# Power_Supply.net
KiCad netlist of a schematic drawn in Altium Designer
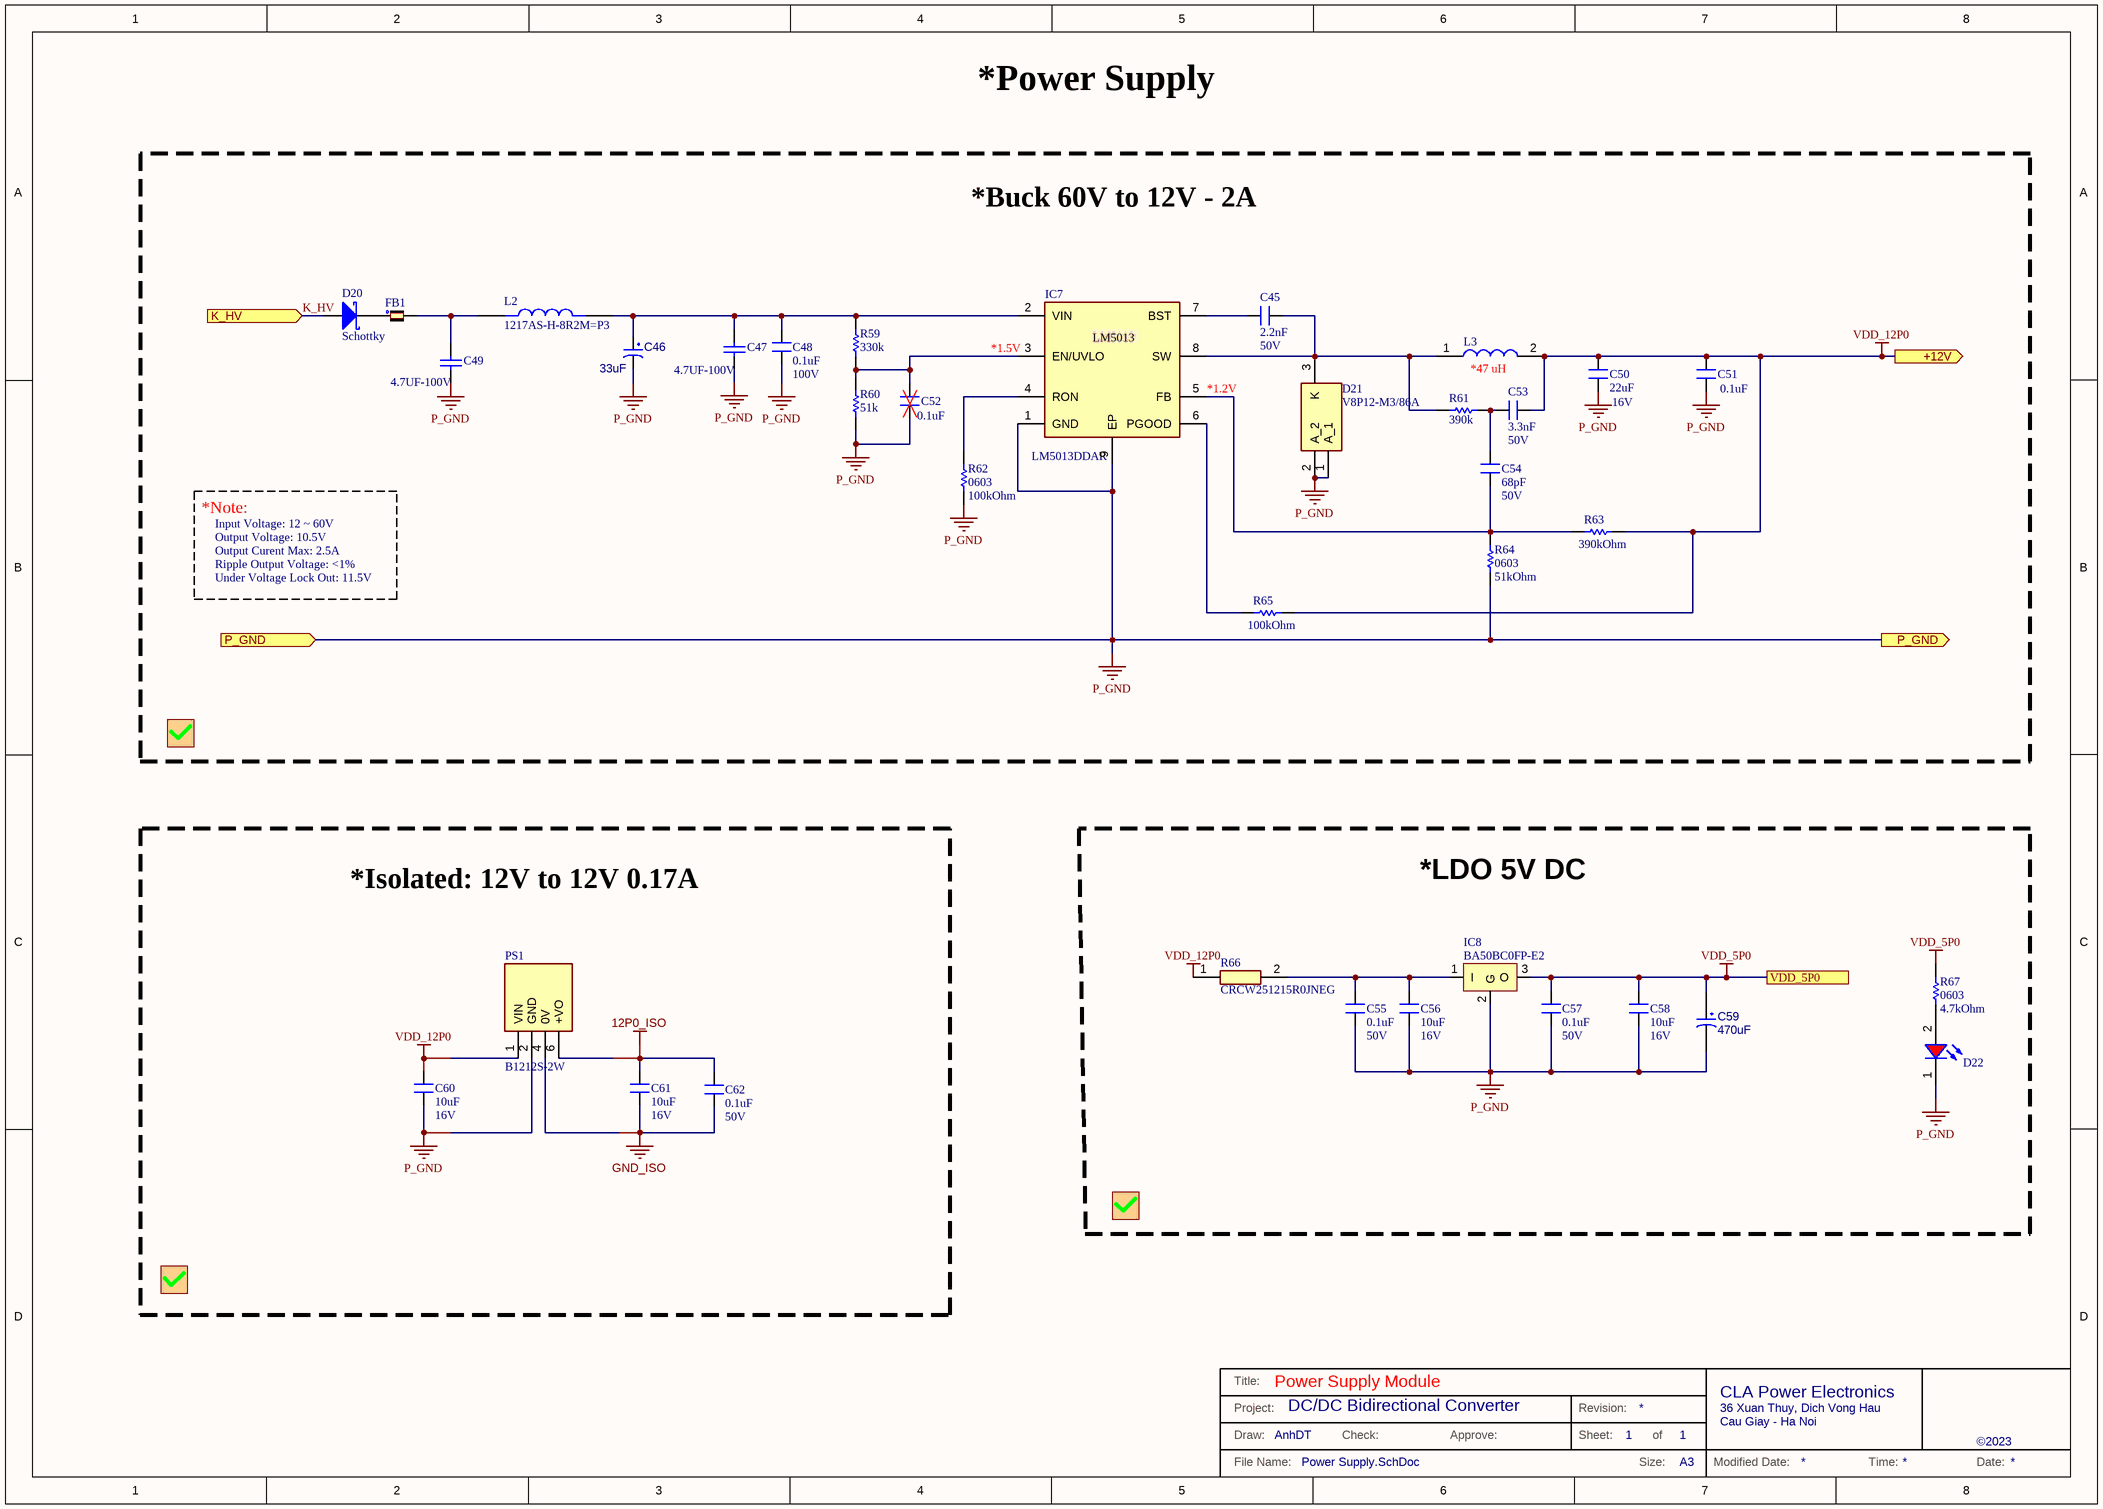
[diagram p0: Power Supply.SchDoc]

(export (version "E")
  (design (tool "Eeschema 10.0.6"))
  (components
    (comp (ref "C45")
      (value "2.2nF")
      (footprint "C_0603")
      (description "CAP CER 2.2nF 50V X7R 0805")
      (fields
        (field (name "MANUFACTURER") "Samsung Electro-Mechanics")
        (field (name "PART NUMBER") "C0805C222J5GEC7800")
        (field (name "ALTIUM_VALUE") "50V")
      )
      (libsource (lib "S1200_Capacitor") (part "Cap_Cer_0805_10pF"))
    )
    (comp (ref "C46")
      (value "33uF")
      (footprint "C_ALU_TH_8p0D11p5")
      (description "CAP ALUM 33UF 20% 80V RADIAL")
      (fields (field (name "MANUFACTURER") "PANASONIC") (field (name "PART NUMBER") "80ZLH33MEFC6.3X11"))
      (libsource (lib "Selex_Component_Lib") (part "Cap_Alu_TH_8P0D3P5_22uF"))
    )
    (comp (ref "C47")
      (value "4.7UF-100V")
      (footprint "C_1210")
      (description "CAP CER 4.7uF 80V X7R 1210")
      (fields
        (field (name "PART NUMBER") "GRM32ER71K475KE14L")
        (field (name "MANUFACTURER") "TDK Corporation")
      )
      (libsource (lib "DC_DC_Power_V3.0") (part "Cap 1210"))
    )
    (comp (ref "C48")
      (value "0.1uF")
      (footprint "C_0805")
      (description "CAP CER 0.1uF 100V X7R 0805")
      (fields (field (name "MANUFACTURER") "Samsung Electro-Mechanics") (field (name "ALTIUM_VALUE") "100V"))
      (libsource (lib "S1200_Capacitor") (part "Cap_Cer_0805_10pF"))
    )
    (comp (ref "C49")
      (value "4.7UF-100V")
      (footprint "C_1210")
      (description "CAP CER 4.7uF 80V X7R 1210")
      (fields
        (field (name "PART NUMBER") "GRM32ER71K475KE14L")
        (field (name "MANUFACTURER") "TDK Corporation")
      )
      (libsource (lib "DC_DC_Power_V3.0") (part "Cap 1210"))
    )
    (comp (ref "C50")
      (value "22uF")
      (footprint "C_1210")
      (description "CAP CER 22uF 16V X7R 1210")
      (fields
        (field (name "MANUFACTURER") "Samsung Electro-Mechanics")
        (field (name "PART NUMBER") "CL32A226KOJNNNE")
        (field (name "ALTIUM_VALUE") "16V")
      )
      (libsource (lib "S1200_Capacitor") (part "Cap_Cer_0805_10pF"))
    )
    (comp (ref "C51")
      (value "0.1uF")
      (footprint "C_0603")
      (description "CAP CER 0.1UF 25V X8R 0603")
      (fields
        (field (name "MANUFACTURER") "Murata Electronics")
        (field (name "PART NUMBER") "GCM188R91E104KA37J")
      )
      (libsource (lib "S1200_Capacitor") (part "Cap_Cer_0603_0.1uF_25V"))
    )
    (comp (ref "C52")
      (value "0.1uF")
      (footprint "C_0603")
      (description "CAP CER 0.1UF 100V X7R 0603")
      (fields
        (field (name "MANUFACTURER") "Murata Electronics")
        (field (name "PART NUMBER") "GRM188R72A104KA35D")
      )
      (libsource (lib "S1200_Capacitor") (part "Cap_Cer_0603_0.1uF_100V"))
    )
    (comp (ref "C53")
      (value "3.3nF")
      (footprint "C_0603")
      (description "CAP CER 0805 3.3NF 50V C0G 1%")
      (fields
        (field (name "MANUFACTURER") "Kemet")
        (field (name "PART NUMBER") "C0805C332F5GECAUTO")
        (field (name "ALTIUM_VALUE") "50V")
      )
      (libsource (lib "S1200_Capacitor") (part "Cap_Cer_0805_10pF"))
    )
    (comp (ref "C54")
      (value "68pF")
      (footprint "C_0603")
      (description "CAP CER 68pF 50V C0G 0603")
      (fields
        (field (name "MANUFACTURER") "Kemet")
        (field (name "PART NUMBER") "CL10C680JB81PNC")
        (field (name "ALTIUM_VALUE") "50V")
      )
      (libsource (lib "S1200_Capacitor") (part "Cap_Cer_0805_10pF"))
    )
    (comp (ref "C55")
      (value "0.1uF")
      (footprint "C_0603")
      (description "CAP CER 0.1uF 50V X7R 0603")
      (fields
        (field (name "MANUFACTURER") "Kemet")
        (field (name "PART NUMBER") "CL10C680JB81PNC")
        (field (name "ALTIUM_VALUE") "50V")
      )
      (libsource (lib "S1200_Capacitor") (part "Cap_Cer_0805_10pF"))
    )
    (comp (ref "C56")
      (value "10uF")
      (footprint "C_0805")
      (description "CAP CER 10uF 16V X7R 0805")
      (fields
        (field (name "MANUFACTURER") "Kemet")
        (field (name "PART NUMBER") "CL21A106KOCLRNC")
        (field (name "ALTIUM_VALUE") "16V")
      )
      (libsource (lib "S1200_Capacitor") (part "Cap_Cer_0805_10pF"))
    )
    (comp (ref "C57")
      (value "0.1uF")
      (footprint "C_0603")
      (description "CAP CER 0.1uF 50V X7R 0603")
      (fields
        (field (name "MANUFACTURER") "Kemet")
        (field (name "PART NUMBER") "CL10C680JB81PNC")
        (field (name "ALTIUM_VALUE") "50V")
      )
      (libsource (lib "S1200_Capacitor") (part "Cap_Cer_0805_10pF"))
    )
    (comp (ref "C58")
      (value "10uF")
      (footprint "C_0805")
      (description "CAP CER 10uF 16V X7R 0805")
      (fields
        (field (name "MANUFACTURER") "Kemet")
        (field (name "PART NUMBER") "CL21A106KOCLRNC")
        (field (name "ALTIUM_VALUE") "16V")
      )
      (libsource (lib "S1200_Capacitor") (part "Cap_Cer_0805_10pF"))
    )
    (comp (ref "C59")
      (value "470uF")
      (footprint "C_ALU_TH_8p0D11p5")
      (description "CAP ALUM 470UF 20% 25V RADIAL")
      (fields (field (name "MANUFACTURER") "Rubycon") (field (name "PART NUMBER") "16YXJ220MT16.3X11"))
      (libsource (lib "Selex_Component_Lib") (part "Cap_Alu_TH_8P0D3P5"))
    )
    (comp (ref "C60")
      (value "10uF")
      (footprint "C_0805")
      (description "CAP CER 2.2uF 50V X7R 0805")
      (fields
        (field (name "MANUFACTURER") "Samsung Electro-Mechanics")
        (field (name "PART NUMBER") "CL31B225KBHNNNE")
        (field (name "ALTIUM_VALUE") "16V")
      )
      (libsource (lib "S1200_Capacitor") (part "Cap_Cer_0805_10pF"))
    )
    (comp (ref "C61")
      (value "10uF")
      (footprint "C_0805")
      (description "CAP CER 4.7uF 50V X7R 0805")
      (fields
        (field (name "MANUFACTURER") "Samsung Electro-Mechanics")
        (field (name "PART NUMBER") "CL31B225KBHNNNE")
        (field (name "ALTIUM_VALUE") "16V")
      )
      (libsource (lib "S1200_Capacitor") (part "Cap_Cer_0805_10pF"))
    )
    (comp (ref "C62")
      (value "0.1uF")
      (footprint "C_0603")
      (description "CAP CER 0.1uF 50V X7R 0603")
      (fields
        (field (name "MANUFACTURER") "Kemet")
        (field (name "PART NUMBER") "CL10C680JB81PNC")
        (field (name "ALTIUM_VALUE") "50V")
      )
      (libsource (lib "S1200_Capacitor") (part "Cap_Cer_0805_10pF"))
    )
    (comp (ref "D20")
      (value "Schottky")
      (footprint "DIODE_Schottky_DO214")
      (description "DIODE SCHOTTKY 100V 3A SMA")
      (fields (field (name "MANUFACTURER") "SMC Diode Solutions") (field (name "PART NUMBER") "SS310"))
      (libsource (lib "S1500_Diode") (part "SS34"))
    )
    (comp (ref "D21")
      (value "V8P12-M3/86A")
      (footprint "V8P12M386A")
      (description "DIODE SCHOTTKY 120V 8A TO277A")
      (fields (field (name "MOUSER PART NUMBER") "78-V8P12-M3/86A"))
      (libsource (lib "*") (part "V8P12-M3_86A"))
    )
    (comp (ref "D22")
      (value "LED-SMD")
      (footprint "SM-LED-0805-Red")
      (description "LED RED DIFFUSED 0805 SMD")
      (fields
        (field (name "MANUFACTURER") "OSRAM Opto Semiconductors Inc.")
        (field (name "PART NUMBER") "LS R976-NR-1")
      )
      (libsource (lib "Sync_Buck") (part "LED-SMD"))
    )
    (comp (ref "FB1")
      (value "FerriteBead_1206_270Ohm")
      (footprint "FERRITEBEAD_1206")
      (description "FERRITE BEAD 270 OHM 1206 1LN")
      (fields
        (field (name "MANUFACTURER") "Murata Electronics")
        (field (name "PART NUMBER") "BLM31KN271SH1L")
      )
      (libsource (lib "S1100_Resistor_FerriteBead") (part "FerriteBead_1206_270Ohm"))
    )
    (comp (ref "IC7")
      (value "LM5013DDAR")
      (footprint "SOIC127P600X170-9N")
      (description "IC REG BUCK ADJ 3.5A 8SO PWR")
      (libsource (lib "Tienanh") (part "LM5012DDAR"))
    )
    (comp (ref "IC8")
      (value "BA50BC0FP-E2")
      (footprint "TO252-123")
      (description "IC REG LINEAR 5V 1A TO252-2")
      (libsource (lib "Motor Control SELEX MOTORS JSC") (part "BA50BC0FP-E2"))
    )
    (comp (ref "L2")
      (value "1217AS-H-8R2M=P3")
      (footprint "IND_1217AS-H-8R2M=P3")
      (description "Inductor with Inductance: 8.2uH Tol. +/-20%, Package: 3131 (8080)")
      (fields (field (name "MF") "Murata"))
      (libsource (lib "1217AS-H-8R2M_P3") (part "1217AS-H-8R2M=P3"))
    )
    (comp (ref "L3")
      (value "~")
      (footprint "SRR1260A470M")
      (description "FIXED IND 47UH 2.5A 100 MOHM SMD")
      (fields (field (name "MANUFACTURER") "Taiyo Yuden") (field (name "PART NUMBER") "CDRH127-470"))
      (libsource (lib "Motor Control SELEX MOTORS JSC") (part "Inductor"))
    )
    (comp (ref "PS1")
      (value "B1212S-2W")
      (footprint "SamacSys:B1212S2W")
      (description "Power Supply")
      (libsource (lib "*") (part "B1212S-2W"))
    )
    (comp (ref "R59")
      (value "330k")
      (footprint "R_0603")
      (description "RES 200K OHM 1% 1/10W 0603")
      (fields (field (name "MANUFACTURER") "YAGEO") (field (name "PART NUMBER") "RC0603FR-13200KL"))
      (libsource (lib "S1100_Resistor_FerriteBead") (part "Resistor_0603_10Ohm 1%"))
    )
    (comp (ref "R60")
      (value "51k")
      (footprint "R_0603")
      (description "RES 24k OHM 1% 1/8W 0603")
      (fields (field (name "MANUFACTURER") "YAGEO") (field (name "PART NUMBER") "RC0603FR-1024KL"))
      (libsource (lib "S1100_Resistor_FerriteBead") (part "Resistor_0603_10Ohm 1%"))
    )
    (comp (ref "R61")
      (value "390k")
      (footprint "R_0603")
      (description "RES 390k OHM 1% 1/8W 0603")
      (fields (field (name "MANUFACTURER") "YAGEO") (field (name "PART NUMBER") "RC0603FR-07390KL"))
      (libsource (lib "S1100_Resistor_FerriteBead") (part "Resistor_0603_10Ohm 1%"))
    )
    (comp (ref "R62")
      (value "0603")
      (footprint "R_0603")
      (description "RES SMD 100K OHM 1% 1/8W 0603")
      (fields
        (field (name "MANUFACTURER") "Vishay Beyschlag/Draloric/BC Components")
        (field (name "PART NUMBER") "MCT06030C1003FP500")
        (field (name "ALTIUM_VALUE") "100kOhm")
      )
      (libsource (lib "S1100_Resistor_FerriteBead") (part "Resistor_0603_100kOhm"))
    )
    (comp (ref "R63")
      (value "390kOhm")
      (footprint "R_0603")
      (description "RES SMD 470K OHM 1% 1/10W 0603")
      (fields (field (name "MANUFACTURER") "Walsin Technology Corporation") (field (name "POWER") "1/10W"))
      (libsource (lib "S1100_Resistor_FerriteBead") (part "Resistor_0603_470kOhm"))
    )
    (comp (ref "R64")
      (value "0603")
      (footprint "R_0603")
      (description "RES SMD 51K OHM 1% 1/8W 0603")
      (fields
        (field (name "MANUFACTURER") "YAGEO")
        (field (name "PART NUMBER") "RC0603FR-0751KL")
        (field (name "ALTIUM_VALUE") "51kOhm")
      )
      (libsource (lib "S1100_Resistor_FerriteBead") (part "Resistor_0603_51kOhm"))
    )
    (comp (ref "R65")
      (value "100kOhm")
      (footprint "R_0603")
      (description "RES SMD 100K OHM 1% 1/8W 0603")
      (fields
        (field (name "MANUFACTURER") "Vishay Beyschlag/Draloric/BC Components")
        (field (name "PART NUMBER") "MCT06030C1003FP500")
      )
      (libsource (lib "S1100_Resistor_FerriteBead") (part "Resistor_0603_100kOhm"))
    )
    (comp (ref "R66")
      (value "CRCW251215R0JNEG")
      (footprint "RESC6332X70N")
      (fields (field (name "MOUSER PART NUMBER") "71-CRCW2512J-15-E3"))
      (libsource (lib "*") (part "CRCW251215R0JNEG"))
    )
    (comp (ref "R67")
      (value "0603")
      (footprint "R_0603")
      (description "RES 2K OHM 1% 1/10W 0603")
      (fields
        (field (name "MANUFACTURER") "YAGEO")
        (field (name "PART NUMBER") "RC0603FR-074K7L")
        (field (name "ALTIUM_VALUE") "4.7kOhm")
      )
      (libsource (lib "S1100_Resistor_FerriteBead") (part "Resistor_0603_4.7kOhm"))
    )
  )
  (nets
    (net (code "1") (name "/K_HV") (class "Default")
      (node (ref "D20") (pin "1") (pinfunction "A_1") (pintype "passive"))
    )
    (net (code "2") (name "12P0_ISO") (class "Default")
      (node (ref "C61") (pin "2") (pinfunction "2_2") (pintype "passive"))
      (node (ref "C62") (pin "2") (pinfunction "2_2") (pintype "passive"))
      (node (ref "PS1") (pin "6") (pinfunction "+VO_6") (pintype "passive"))
    )
    (net (code "3") (name "GND_ISO") (class "Default")
      (node (ref "C61") (pin "1") (pinfunction "1_1") (pintype "passive"))
      (node (ref "C62") (pin "1") (pinfunction "1_1") (pintype "passive"))
      (node (ref "PS1") (pin "4") (pinfunction "0V_4") (pintype "passive"))
    )
    (net (code "4") (name "Net-(C49-Pad2)") (class "Default")
      (node (ref "C49") (pin "2") (pinfunction "2_2") (pintype "passive"))
      (node (ref "FB1") (pin "2") (pinfunction "2_2") (pintype "passive"))
      (node (ref "L2") (pin "1") (pinfunction "1_1") (pintype "passive"))
    )
    (net (code "5") (name "Net-(C53-Pad1)") (class "Default")
      (node (ref "C53") (pin "1") (pinfunction "1_1") (pintype "passive"))
      (node (ref "C54") (pin "2") (pinfunction "2_2") (pintype "passive"))
      (node (ref "R61") (pin "1") (pinfunction "1_1") (pintype "passive"))
    )
    (net (code "6") (name "Net-(D20-K)") (class "Default")
      (node (ref "D20") (pin "2") (pinfunction "K_2") (pintype "passive"))
      (node (ref "FB1") (pin "1") (pinfunction "1_1") (pintype "passive"))
    )
    (net (code "7") (name "Net-(D21-K)") (class "Default")
      (node (ref "C45") (pin "1") (pinfunction "1_1") (pintype "passive"))
      (node (ref "D21") (pin "3") (pinfunction "K_3") (pintype "passive"))
      (node (ref "IC7") (pin "8") (pinfunction "SW_8") (pintype "passive"))
      (node (ref "L3") (pin "1") (pinfunction "1_1") (pintype "passive"))
      (node (ref "R61") (pin "2") (pinfunction "2_2") (pintype "passive"))
    )
    (net (code "8") (name "Net-(D22-A)") (class "Default")
      (node (ref "D22") (pin "2") (pinfunction "A_2") (pintype "passive"))
      (node (ref "R67") (pin "1") (pinfunction "1_1") (pintype "passive"))
    )
    (net (code "9") (name "Net-(IC7-BST)") (class "Default")
      (node (ref "C45") (pin "2") (pinfunction "2_2") (pintype "passive"))
      (node (ref "IC7") (pin "7") (pinfunction "BST_7") (pintype "passive"))
    )
    (net (code "10") (name "Net-(IC7-EN{slash}UVLO)") (class "Default")
      (node (ref "C52") (pin "1") (pinfunction "1_1") (pintype "passive"))
      (node (ref "IC7") (pin "3") (pinfunction "EN/UVLO_3") (pintype "passive"))
      (node (ref "R59") (pin "1") (pinfunction "1_1") (pintype "passive"))
      (node (ref "R60") (pin "2") (pinfunction "2_2") (pintype "passive"))
    )
    (net (code "11") (name "Net-(IC7-FB)") (class "Default")
      (node (ref "C54") (pin "1") (pinfunction "1_1") (pintype "passive"))
      (node (ref "IC7") (pin "5") (pinfunction "FB_5") (pintype "passive"))
      (node (ref "R63") (pin "1") (pinfunction "1_1") (pintype "passive"))
      (node (ref "R64") (pin "2") (pinfunction "2_2") (pintype "passive"))
    )
    (net (code "12") (name "Net-(IC7-PGOOD)") (class "Default")
      (node (ref "IC7") (pin "6") (pinfunction "PGOOD_6") (pintype "passive"))
      (node (ref "R65") (pin "2") (pinfunction "2_2") (pintype "passive"))
    )
    (net (code "13") (name "Net-(IC7-RON)") (class "Default")
      (node (ref "IC7") (pin "4") (pinfunction "RON_4") (pintype "passive"))
      (node (ref "R62") (pin "2") (pinfunction "2_2") (pintype "passive"))
    )
    (net (code "14") (name "Net-(IC7-VIN)") (class "Default")
      (node (ref "C46") (pin "1") (pinfunction "1_1") (pintype "passive"))
      (node (ref "C47") (pin "2") (pinfunction "2_2") (pintype "passive"))
      (node (ref "C48") (pin "2") (pinfunction "2_2") (pintype "passive"))
      (node (ref "IC7") (pin "2") (pinfunction "VIN_2") (pintype "passive"))
      (node (ref "L2") (pin "2") (pinfunction "2_2") (pintype "passive"))
      (node (ref "R59") (pin "2") (pinfunction "2_2") (pintype "passive"))
    )
    (net (code "15") (name "Net-(IC8-I)") (class "Default")
      (node (ref "C55") (pin "2") (pinfunction "2_2") (pintype "passive"))
      (node (ref "C56") (pin "2") (pinfunction "2_2") (pintype "passive"))
      (node (ref "IC8") (pin "1") (pinfunction "I_1") (pintype "power_in"))
      (node (ref "R66") (pin "2") (pinfunction "2_2") (pintype "passive"))
    )
    (net (code "16") (name "P_GND") (class "Default")
      (node (ref "C46") (pin "2") (pinfunction "2_2") (pintype "passive"))
      (node (ref "C47") (pin "1") (pinfunction "1_1") (pintype "passive"))
      (node (ref "C48") (pin "1") (pinfunction "1_1") (pintype "passive"))
      (node (ref "C49") (pin "1") (pinfunction "1_1") (pintype "passive"))
      (node (ref "C50") (pin "1") (pinfunction "1_1") (pintype "passive"))
      (node (ref "C51") (pin "1") (pinfunction "1_1") (pintype "passive"))
      (node (ref "C52") (pin "2") (pinfunction "2_2") (pintype "passive"))
      (node (ref "C55") (pin "1") (pinfunction "1_1") (pintype "passive"))
      (node (ref "C56") (pin "1") (pinfunction "1_1") (pintype "passive"))
      (node (ref "C57") (pin "1") (pinfunction "1_1") (pintype "passive"))
      (node (ref "C58") (pin "1") (pinfunction "1_1") (pintype "passive"))
      (node (ref "C59") (pin "2") (pinfunction "2_2") (pintype "passive"))
      (node (ref "C60") (pin "1") (pinfunction "1_1") (pintype "passive"))
      (node (ref "D21") (pin "1") (pinfunction "A_1_1") (pintype "passive"))
      (node (ref "D21") (pin "2") (pinfunction "A_2_2") (pintype "passive"))
      (node (ref "D22") (pin "1") (pinfunction "K_1") (pintype "passive"))
      (node (ref "IC7") (pin "1") (pinfunction "GND_1") (pintype "passive"))
      (node (ref "IC7") (pin "9") (pinfunction "EP_9") (pintype "passive"))
      (node (ref "IC8") (pin "2") (pinfunction "G_2") (pintype "power_in"))
      (node (ref "PS1") (pin "2") (pinfunction "GND_2") (pintype "passive"))
      (node (ref "R60") (pin "1") (pinfunction "1_1") (pintype "passive"))
      (node (ref "R62") (pin "1") (pinfunction "1_1") (pintype "passive"))
      (node (ref "R64") (pin "1") (pinfunction "1_1") (pintype "passive"))
    )
    (net (code "17") (name "VDD_5P0") (class "Default")
      (node (ref "C57") (pin "2") (pinfunction "2_2") (pintype "passive"))
      (node (ref "C58") (pin "2") (pinfunction "2_2") (pintype "passive"))
      (node (ref "C59") (pin "1") (pinfunction "1_1") (pintype "passive"))
      (node (ref "IC8") (pin "3") (pinfunction "O_3") (pintype "power_in"))
      (node (ref "R67") (pin "2") (pinfunction "2_2") (pintype "passive"))
    )
    (net (code "18") (name "VDD_12P0") (class "Default")
      (node (ref "C50") (pin "2") (pinfunction "2_2") (pintype "passive"))
      (node (ref "C51") (pin "2") (pinfunction "2_2") (pintype "passive"))
      (node (ref "C53") (pin "2") (pinfunction "2_2") (pintype "passive"))
      (node (ref "C60") (pin "2") (pinfunction "2_2") (pintype "passive"))
      (node (ref "L3") (pin "2") (pinfunction "2_2") (pintype "passive"))
      (node (ref "PS1") (pin "1") (pinfunction "VIN_1") (pintype "passive"))
      (node (ref "R63") (pin "2") (pinfunction "2_2") (pintype "passive"))
      (node (ref "R65") (pin "1") (pinfunction "1_1") (pintype "passive"))
      (node (ref "R66") (pin "1") (pinfunction "1_1") (pintype "passive"))
    )
  )
)
